# controller15_2.net
KiCad netlist of a schematic drawn in EAGLE
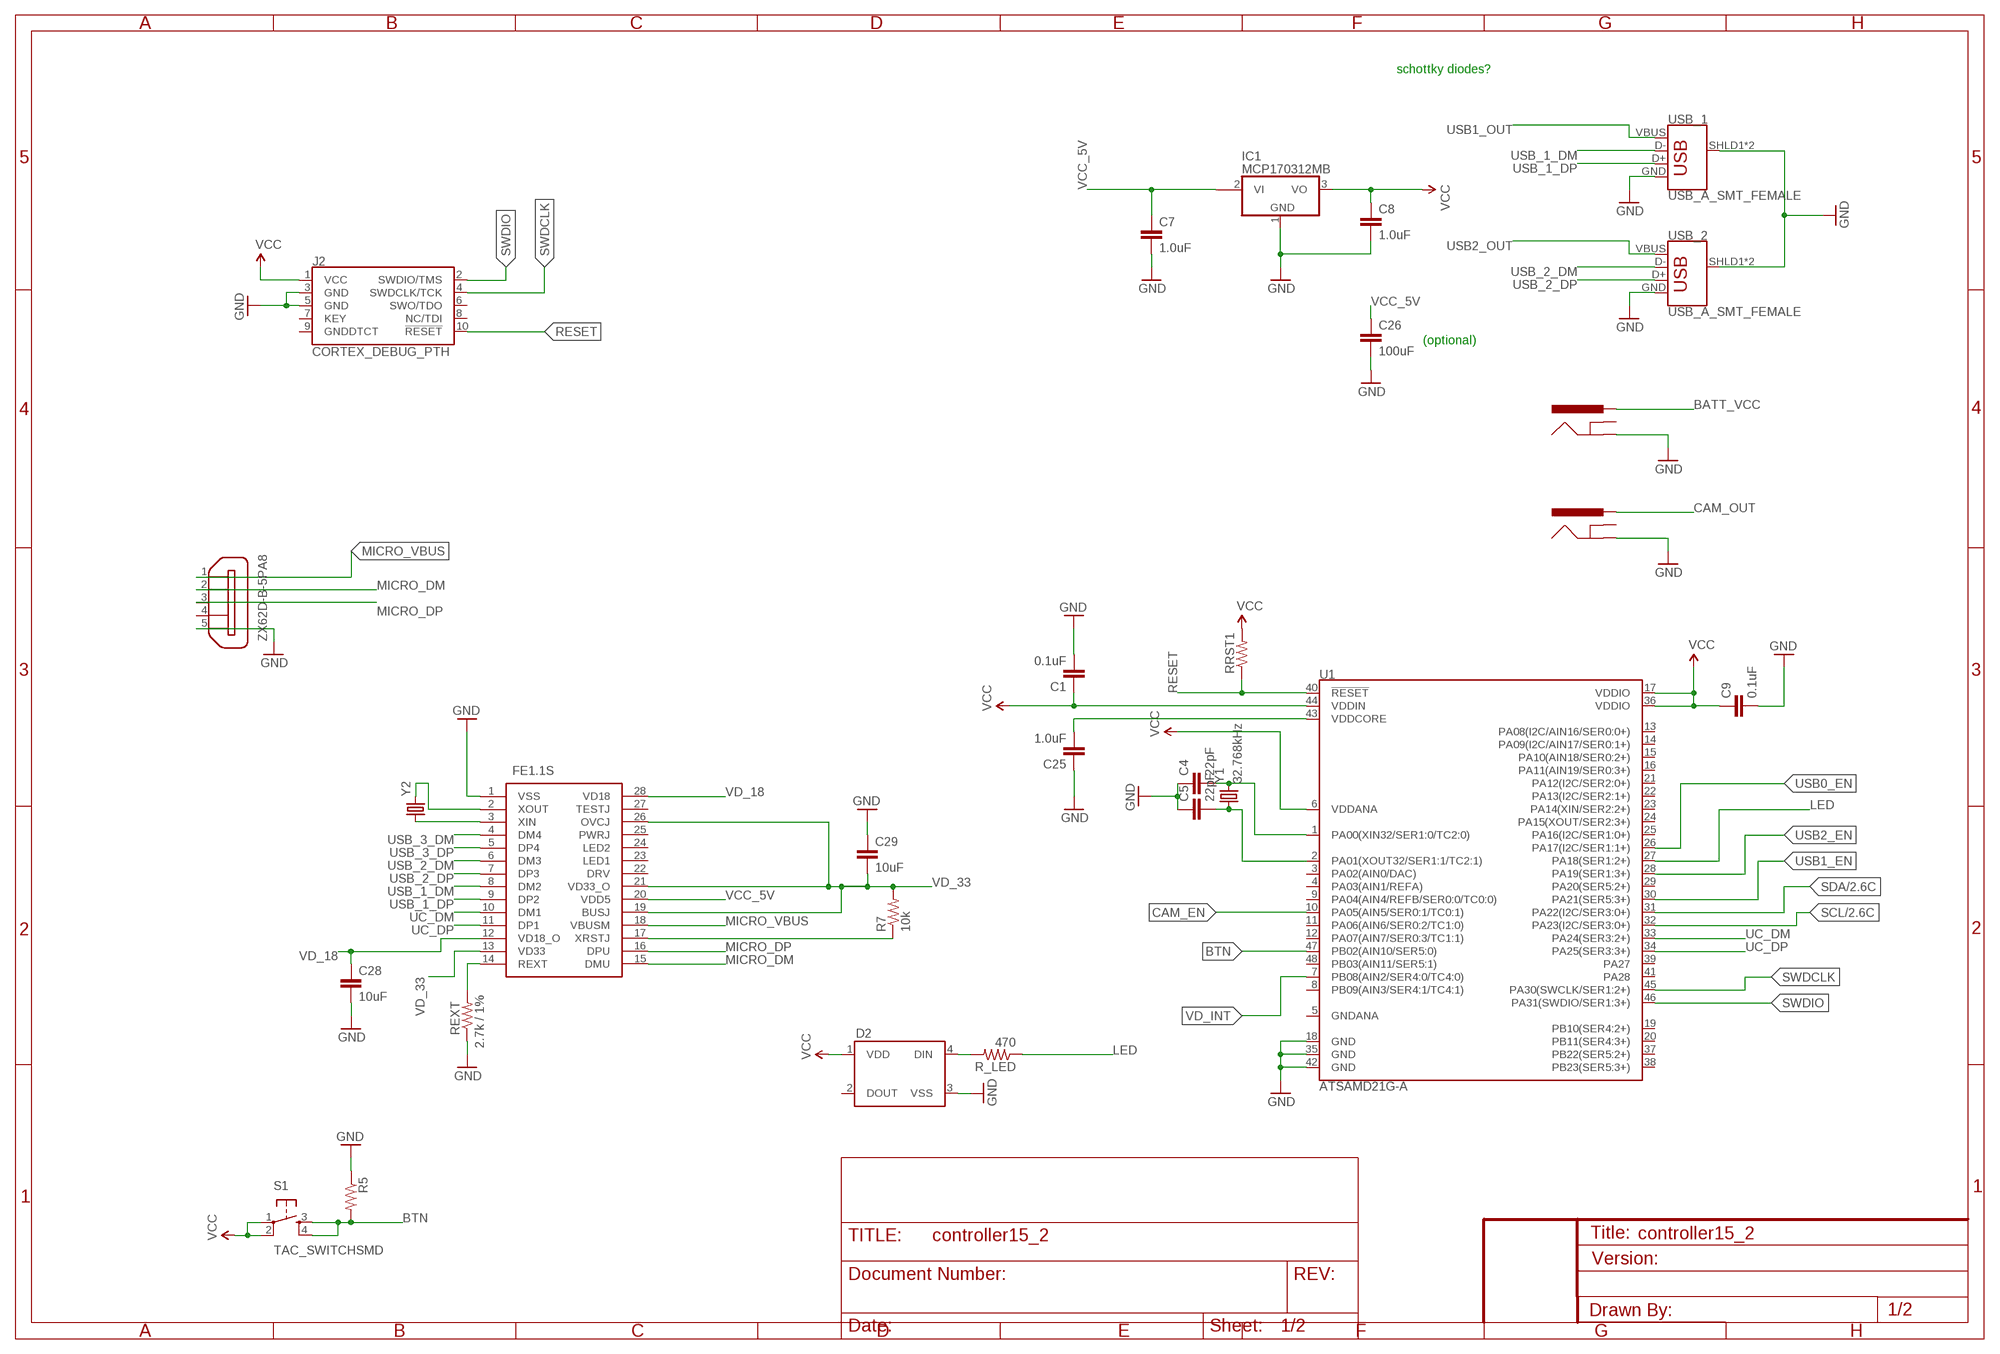
[diagram p0: schematic, sheet 1]
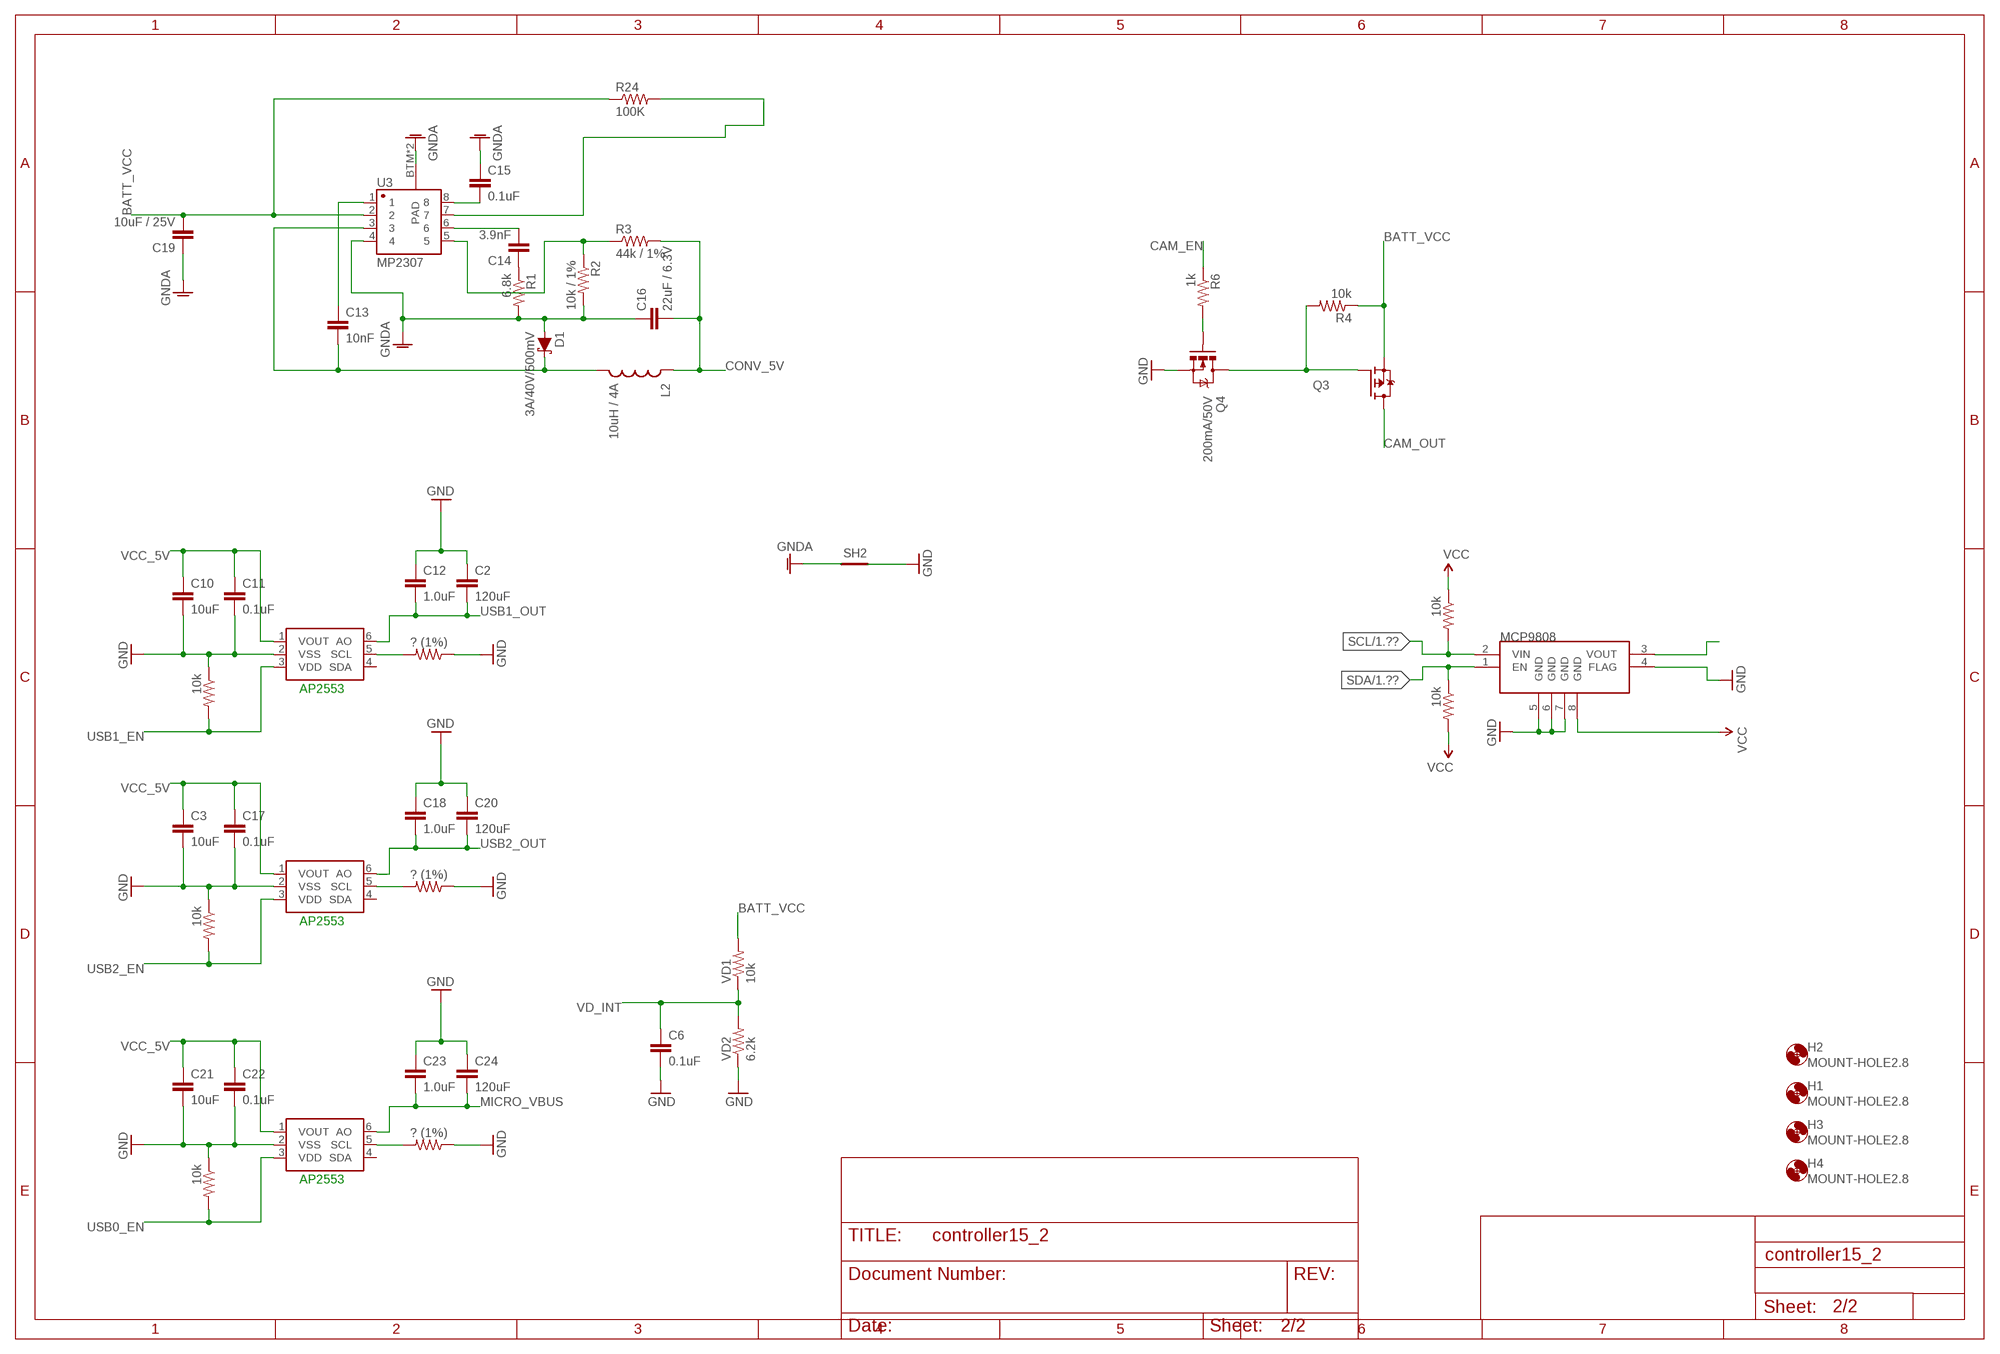
[diagram p1: schematic, sheet 2]

(export (version "E")
  (design (tool "Eeschema 10.0.6"))
  (components
    (comp (ref "C1")
      (value "0.1uF")
      (footprint "eagle-import:0805")
      (libsource (lib "eagle-import") (part "1.0UF-0805-25V-10%"))
    )
    (comp (ref "C4")
      (value "22pF")
      (footprint "eagle-import:0805")
      (libsource (lib "eagle-import") (part "SparkFun-Passives_CAP0805"))
    )
    (comp (ref "C5")
      (value "22pF")
      (footprint "eagle-import:0805")
      (libsource (lib "eagle-import") (part "SparkFun-Passives_CAP0805"))
    )
    (comp (ref "C7")
      (value "1.0uF")
      (footprint "eagle-import:1206")
      (libsource (lib "eagle-import") (part "1.0UF-1206-50V-10%"))
    )
    (comp (ref "C8")
      (value "1.0uF")
      (footprint "eagle-import:1206")
      (libsource (lib "eagle-import") (part "1.0UF-1206-50V-10%"))
    )
    (comp (ref "C9")
      (value "0.1uF")
      (footprint "eagle-import:0805")
      (libsource (lib "eagle-import") (part "1.0UF-0805-25V-10%"))
    )
    (comp (ref "C25")
      (value "1.0uF")
      (footprint "eagle-import:0805")
      (libsource (lib "eagle-import") (part "1.0UF-0805-25V-10%"))
    )
    (comp (ref "C26")
      (value "100uF")
      (footprint "eagle-import:1206")
      (libsource (lib "eagle-import") (part "1.0UF-1206-50V-10%"))
    )
    (comp (ref "C28")
      (value "10uF")
      (footprint "eagle-import:0805")
      (libsource (lib "eagle-import") (part "1.0UF-0805-25V-10%"))
    )
    (comp (ref "C29")
      (value "10uF")
      (footprint "eagle-import:0805")
      (libsource (lib "eagle-import") (part "1.0UF-0805-25V-10%"))
    )
    (comp (ref "D2")
      (value "WS2812B")
      (footprint "eagle-import:WS2812B")
      (libsource (lib "eagle-import") (part "WS2812B"))
    )
    (comp (ref "IC1")
      (value "MCP170312MB")
      (footprint "eagle-import:SOT89")
      (libsource (lib "eagle-import") (part "MCP1703MB12"))
    )
    (comp (ref "IC3")
      (value "FE1.1S")
      (footprint "eagle-import:SOP64P600X175-28N")
      (libsource (lib "eagle-import") (part "FE1.1S"))
    )
    (comp (ref "J2")
      (value "CORTEX_DEBUG_PTH")
      (footprint "eagle-import:2X5-PTH-1.27MM")
      (libsource (lib "eagle-import") (part "CORTEX_DEBUG_PTH"))
    )
    (comp (ref "J3")
      (value "POWER_JACKPTH_BREAD")
      (footprint "eagle-import:POWER_JACK_PTH_BREAD")
      (libsource (lib "eagle-import") (part "POWER_JACKPTH_BREAD"))
    )
    (comp (ref "J4")
      (value "POWER_JACKPTH_BREAD")
      (footprint "eagle-import:POWER_JACK_PTH_BREAD")
      (libsource (lib "eagle-import") (part "POWER_JACKPTH_BREAD"))
    )
    (comp (ref "R5")
      (value "RESISTOR0805-RES")
      (footprint "eagle-import:0805")
      (libsource (lib "eagle-import") (part "RESISTOR0805-RES"))
    )
    (comp (ref "R7")
      (value "10k")
      (footprint "eagle-import:0805")
      (libsource (lib "eagle-import") (part "RESISTOR0805-RES"))
    )
    (comp (ref "REXT")
      (value "2.7k / 1%")
      (footprint "eagle-import:0805")
      (libsource (lib "eagle-import") (part "RESISTOR0805-RES"))
    )
    (comp (ref "RRST1")
      (value "RESISTOR0805-RES")
      (footprint "eagle-import:0805")
      (libsource (lib "eagle-import") (part "RESISTOR0805-RES"))
    )
    (comp (ref "R_LED")
      (value "470")
      (footprint "eagle-import:0805")
      (libsource (lib "eagle-import") (part "SparkFun-Resistors_RESISTOR0805-RES"))
    )
    (comp (ref "S1")
      (value "TAC_SWITCHSMD")
      (footprint "eagle-import:TACTILE-SWITCH-SMD")
      (libsource (lib "eagle-import") (part "TAC_SWITCHSMD"))
    )
    (comp (ref "U1")
      (value "ATSAMD21G-A")
      (footprint "eagle-import:TQFP-48")
      (libsource (lib "eagle-import") (part "ATSAMD21G-A"))
    )
    (comp (ref "USB_1")
      (value "USB_A_SMT_FEMALE")
      (footprint "eagle-import:USB-A-S-SILK-FEMALE")
      (libsource (lib "eagle-import") (part "USB_A_SMT_FEMALE"))
    )
    (comp (ref "USB_2")
      (value "USB_A_SMT_FEMALE")
      (footprint "eagle-import:USB-A-S-SILK-FEMALE")
      (libsource (lib "eagle-import") (part "USB_A_SMT_FEMALE"))
    )
    (comp (ref "X2")
      (value "ZX62D-B-5PA8")
      (footprint "eagle-import:ZX62D-B-5PA8")
      (fields (field (name "MF") "Hirose"))
      (libsource (lib "eagle-import") (part "ZX62D-B-5PA8"))
    )
    (comp (ref "Y1")
      (value "32.768kHz")
      (footprint "eagle-import:CRYSTAL-SMD-3.2X1.5MM")
      (libsource (lib "eagle-import") (part "CRYSTAL3.2X1.5MM"))
    )
    (comp (ref "Y2")
      (value "12MHz")
      (footprint "eagle-import:HC49U-V")
      (libsource (lib "eagle-import") (part "CRYSTALHC49UV"))
    )
    (comp (ref "AP1")
      (value "MCP4725")
      (footprint "eagle-import:SOT23-6")
      (libsource (lib "eagle-import") (part "MCP4725SOT-23"))
    )
    (comp (ref "AP2")
      (value "MCP4725")
      (footprint "eagle-import:SOT23-6")
      (libsource (lib "eagle-import") (part "MCP4725SOT-23"))
    )
    (comp (ref "AP2553")
      (value "MCP4725")
      (footprint "eagle-import:SOT23-6")
      (libsource (lib "eagle-import") (part "MCP4725SOT-23"))
    )
    (comp (ref "C2")
      (value "120uF")
      (footprint "eagle-import:1206")
      (libsource (lib "eagle-import") (part "1.0UF-1206-50V-10%"))
    )
    (comp (ref "C3")
      (value "10uF")
      (footprint "eagle-import:1206")
      (libsource (lib "eagle-import") (part "1.0UF-1206-50V-10%"))
    )
    (comp (ref "C6")
      (value "0.1uF")
      (footprint "eagle-import:1206")
      (libsource (lib "eagle-import") (part "CAP1206"))
    )
    (comp (ref "C10")
      (value "10uF")
      (footprint "eagle-import:1206")
      (libsource (lib "eagle-import") (part "1.0UF-1206-50V-10%"))
    )
    (comp (ref "C11")
      (value "0.1uF")
      (footprint "eagle-import:0805")
      (libsource (lib "eagle-import") (part "1.0UF-0805-25V-10%"))
    )
    (comp (ref "C12")
      (value "1.0uF")
      (footprint "eagle-import:1206")
      (libsource (lib "eagle-import") (part "1.0UF-1206-50V-10%"))
    )
    (comp (ref "C13")
      (value "10nF")
      (footprint "eagle-import:1206")
      (libsource (lib "eagle-import") (part "CAP1206"))
    )
    (comp (ref "C14")
      (value "3.9nF")
      (footprint "eagle-import:1206")
      (libsource (lib "eagle-import") (part "CAP1206"))
    )
    (comp (ref "C15")
      (value "0.1uF")
      (footprint "eagle-import:1206")
      (libsource (lib "eagle-import") (part "CAP1206"))
    )
    (comp (ref "C16")
      (value "22uF / 6.3V")
      (footprint "eagle-import:1210")
      (libsource (lib "eagle-import") (part "CAP1210"))
    )
    (comp (ref "C17")
      (value "0.1uF")
      (footprint "eagle-import:0805")
      (libsource (lib "eagle-import") (part "1.0UF-0805-25V-10%"))
    )
    (comp (ref "C18")
      (value "1.0uF")
      (footprint "eagle-import:1206")
      (libsource (lib "eagle-import") (part "1.0UF-1206-50V-10%"))
    )
    (comp (ref "C19")
      (value "10uF / 25V")
      (footprint "eagle-import:1210")
      (libsource (lib "eagle-import") (part "CAP1210"))
    )
    (comp (ref "C20")
      (value "120uF")
      (footprint "eagle-import:1206")
      (libsource (lib "eagle-import") (part "1.0UF-1206-50V-10%"))
    )
    (comp (ref "C21")
      (value "10uF")
      (footprint "eagle-import:1206")
      (libsource (lib "eagle-import") (part "1.0UF-1206-50V-10%"))
    )
    (comp (ref "C22")
      (value "0.1uF")
      (footprint "eagle-import:0805")
      (libsource (lib "eagle-import") (part "1.0UF-0805-25V-10%"))
    )
    (comp (ref "C23")
      (value "1.0uF")
      (footprint "eagle-import:1206")
      (libsource (lib "eagle-import") (part "1.0UF-1206-50V-10%"))
    )
    (comp (ref "C24")
      (value "120uF")
      (footprint "eagle-import:1206")
      (libsource (lib "eagle-import") (part "1.0UF-1206-50V-10%"))
    )
    (comp (ref "D1")
      (value "3A/40V/500mV")
      (footprint "eagle-import:SMA-DIODE")
      (libsource (lib "eagle-import") (part "DIODE-SCHOTTKY-B340A"))
    )
    (comp (ref "H1")
      (value "MOUNT-HOLE2.8")
      (footprint "eagle-import:2,8")
      (libsource (lib "eagle-import") (part "MOUNT-HOLE2.8"))
    )
    (comp (ref "H2")
      (value "MOUNT-HOLE2.8")
      (footprint "eagle-import:2,8")
      (libsource (lib "eagle-import") (part "MOUNT-HOLE2.8"))
    )
    (comp (ref "H3")
      (value "MOUNT-HOLE2.8")
      (footprint "eagle-import:2,8")
      (libsource (lib "eagle-import") (part "MOUNT-HOLE2.8"))
    )
    (comp (ref "H4")
      (value "MOUNT-HOLE2.8")
      (footprint "eagle-import:2,8")
      (libsource (lib "eagle-import") (part "MOUNT-HOLE2.8"))
    )
    (comp (ref "L2")
      (value "10uH / 4A")
      (footprint "eagle-import:SRU1038")
      (libsource (lib "eagle-import") (part "INDUCTORSRU1038"))
    )
    (comp (ref "MCP9808")
      (value "V_REG_MIC5216")
      (footprint "eagle-import:MSOP8")
      (libsource (lib "eagle-import") (part "V_REG_MIC5216"))
    )
    (comp (ref "Q3")
      (value "FDD4141TO252")
      (footprint "eagle-import:TO252")
      (libsource (lib "eagle-import") (part "FDD4141TO252"))
    )
    (comp (ref "Q4")
      (value "200mA/50V")
      (footprint "eagle-import:SOT23-3")
      (libsource (lib "eagle-import") (part "MOSFET-NCHANNELBSS138"))
    )
    (comp (ref "R1")
      (value "6.8k")
      (footprint "eagle-import:1206")
      (libsource (lib "eagle-import") (part "SparkFun-Resistors_RESISTOR1206"))
    )
    (comp (ref "R2")
      (value "10k / 1%")
      (footprint "eagle-import:1206")
      (libsource (lib "eagle-import") (part "SparkFun-Resistors_RESISTOR1206"))
    )
    (comp (ref "R3")
      (value "44k / 1%")
      (footprint "eagle-import:1206")
      (libsource (lib "eagle-import") (part "SparkFun-Resistors_RESISTOR1206"))
    )
    (comp (ref "R4")
      (value "10k")
      (footprint "eagle-import:0805")
      (libsource (lib "eagle-import") (part "SparkFun-Resistors_RESISTOR0805-RES"))
    )
    (comp (ref "R6")
      (value "1k")
      (footprint "eagle-import:0805")
      (libsource (lib "eagle-import") (part "SparkFun-Resistors_RESISTOR0805-RES"))
    )
    (comp (ref "R24")
      (value "100K")
      (footprint "eagle-import:1206")
      (libsource (lib "eagle-import") (part "SparkFun-Resistors_RESISTOR1206"))
    )
    (comp (ref "R_I2C_1")
      (value "10k")
      (footprint "eagle-import:0805")
      (libsource (lib "eagle-import") (part "RESISTOR0805-RES"))
    )
    (comp (ref "R_I2C_2")
      (value "10k")
      (footprint "eagle-import:0805")
      (libsource (lib "eagle-import") (part "RESISTOR0805-RES"))
    )
    (comp (ref "R_MOSFET_USB1")
      (value "? (1%)")
      (footprint "eagle-import:0805")
      (libsource (lib "eagle-import") (part "RESISTOR0805-RES"))
    )
    (comp (ref "R_MOSFET_USB2")
      (value "? (1%)")
      (footprint "eagle-import:0805")
      (libsource (lib "eagle-import") (part "RESISTOR0805-RES"))
    )
    (comp (ref "R_MOSFET_USB3")
      (value "10k")
      (footprint "eagle-import:0805")
      (libsource (lib "eagle-import") (part "RESISTOR0805-RES"))
    )
    (comp (ref "R_MOSFET_USB4")
      (value "10k")
      (footprint "eagle-import:0805")
      (libsource (lib "eagle-import") (part "RESISTOR0805-RES"))
    )
    (comp (ref "R_MOSFET_USB5")
      (value "? (1%)")
      (footprint "eagle-import:0805")
      (libsource (lib "eagle-import") (part "RESISTOR0805-RES"))
    )
    (comp (ref "R_MOSFET_USB6")
      (value "10k")
      (footprint "eagle-import:0805")
      (libsource (lib "eagle-import") (part "RESISTOR0805-RES"))
    )
    (comp (ref "SH2")
      (value "SHORT-HT5")
      (footprint "eagle-import:SHORT_TOP-50")
      (libsource (lib "eagle-import") (part "SHORT-HT5"))
    )
    (comp (ref "U3")
      (value "MP2307")
      (footprint "eagle-import:SO08")
      (libsource (lib "eagle-import") (part "GENERIC-SOIC8MSGEQ7N-FILTER"))
    )
    (comp (ref "VD1")
      (value "10k")
      (footprint "eagle-import:1206")
      (libsource (lib "eagle-import") (part "RESISTOR1206"))
    )
    (comp (ref "VD2")
      (value "6.2k")
      (footprint "eagle-import:1206")
      (libsource (lib "eagle-import") (part "RESISTOR1206"))
    )
  )
  (nets
    (net (code "1") (name "BATT_VCC") (class "Default")
      (node (ref "C19") (pin "2") (pinfunction "2_2") (pintype "passive"))
      (node (ref "J4") (pin "PWR") (pinfunction "PWR_PWR") (pintype "bidirectional"))
      (node (ref "Q3") (pin "2") (pinfunction "S_2") (pintype "passive"))
      (node (ref "R24") (pin "1") (pinfunction "1_1") (pintype "passive"))
      (node (ref "R4") (pin "1") (pinfunction "1_1") (pintype "passive"))
      (node (ref "U3") (pin "2") (pinfunction "2_2") (pintype "bidirectional"))
      (node (ref "VD1") (pin "2") (pinfunction "2_2") (pintype "passive"))
    )
    (net (code "2") (name "BTN") (class "Default")
      (node (ref "R5") (pin "2") (pinfunction "2_2") (pintype "passive"))
      (node (ref "S1") (pin "3") (pinfunction "3_3") (pintype "passive"))
      (node (ref "S1") (pin "4") (pinfunction "4_4") (pintype "passive"))
      (node (ref "U1") (pin "47") (pinfunction "PB02(AIN10/SER5:0)_47") (pintype "bidirectional"))
    )
    (net (code "3") (name "CAM_EN") (class "Default")
      (node (ref "R6") (pin "1") (pinfunction "1_1") (pintype "passive"))
      (node (ref "U1") (pin "10") (pinfunction "PA05(AIN5/SER0:1/TC0:1)_10") (pintype "bidirectional"))
    )
    (net (code "4") (name "CAM_OUT") (class "Default")
      (node (ref "J3") (pin "PWR") (pinfunction "PWR_PWR") (pintype "bidirectional"))
      (node (ref "Q3") (pin "3") (pinfunction "D_3") (pintype "passive"))
    )
    (net (code "5") (name "CONV_5V") (class "Default")
      (node (ref "C16") (pin "2") (pinfunction "2_2") (pintype "passive"))
      (node (ref "L2") (pin "1") (pinfunction "1_1") (pintype "passive"))
      (node (ref "R3") (pin "2") (pinfunction "2_2") (pintype "passive"))
    )
    (net (code "6") (name "GND") (class "Default")
      (node (ref "AP1") (pin "2") (pinfunction "VSS_2") (pintype "bidirectional"))
      (node (ref "AP2") (pin "2") (pinfunction "VSS_2") (pintype "bidirectional"))
      (node (ref "AP2553") (pin "2") (pinfunction "VSS_2") (pintype "bidirectional"))
      (node (ref "C1") (pin "2") (pinfunction "2_2") (pintype "passive"))
      (node (ref "C10") (pin "2") (pinfunction "2_2") (pintype "passive"))
      (node (ref "C11") (pin "2") (pinfunction "2_2") (pintype "passive"))
      (node (ref "C12") (pin "1") (pinfunction "1_1") (pintype "passive"))
      (node (ref "C17") (pin "2") (pinfunction "2_2") (pintype "passive"))
      (node (ref "C18") (pin "1") (pinfunction "1_1") (pintype "passive"))
      (node (ref "C2") (pin "1") (pinfunction "1_1") (pintype "passive"))
      (node (ref "C20") (pin "1") (pinfunction "1_1") (pintype "passive"))
      (node (ref "C21") (pin "2") (pinfunction "2_2") (pintype "passive"))
      (node (ref "C22") (pin "2") (pinfunction "2_2") (pintype "passive"))
      (node (ref "C23") (pin "1") (pinfunction "1_1") (pintype "passive"))
      (node (ref "C24") (pin "1") (pinfunction "1_1") (pintype "passive"))
      (node (ref "C25") (pin "1") (pinfunction "1_1") (pintype "passive"))
      (node (ref "C26") (pin "2") (pinfunction "2_2") (pintype "passive"))
      (node (ref "C28") (pin "2") (pinfunction "2_2") (pintype "passive"))
      (node (ref "C29") (pin "1") (pinfunction "1_1") (pintype "passive"))
      (node (ref "C3") (pin "2") (pinfunction "2_2") (pintype "passive"))
      (node (ref "C4") (pin "1") (pinfunction "1_1") (pintype "passive"))
      (node (ref "C5") (pin "1") (pinfunction "1_1") (pintype "passive"))
      (node (ref "C6") (pin "2") (pinfunction "2_2") (pintype "passive"))
      (node (ref "C7") (pin "2") (pinfunction "2_2") (pintype "passive"))
      (node (ref "C8") (pin "2") (pinfunction "2_2") (pintype "passive"))
      (node (ref "C9") (pin "2") (pinfunction "2_2") (pintype "passive"))
      (node (ref "D2") (pin "3") (pinfunction "VSS_3") (pintype "power_in"))
      (node (ref "IC1") (pin "1") (pinfunction "GND_1") (pintype "passive"))
      (node (ref "IC3") (pin "1") (pinfunction "VSS_1") (pintype "bidirectional"))
      (node (ref "J2") (pin "3") (pinfunction "GND_3") (pintype "bidirectional"))
      (node (ref "J2") (pin "5") (pinfunction "GND_5") (pintype "bidirectional"))
      (node (ref "J3") (pin "GND") (pinfunction "GND_GND") (pintype "bidirectional"))
      (node (ref "J4") (pin "GND") (pinfunction "GND_GND") (pintype "bidirectional"))
      (node (ref "MCP9808") (pin "4") (pinfunction "FLAG_4") (pintype "bidirectional"))
      (node (ref "MCP9808") (pin "5") (pinfunction "GND_5") (pintype "bidirectional"))
      (node (ref "MCP9808") (pin "6") (pinfunction "GND_6") (pintype "bidirectional"))
      (node (ref "MCP9808") (pin "7") (pinfunction "GND_7") (pintype "bidirectional"))
      (node (ref "Q4") (pin "2") (pinfunction "S_2") (pintype "passive"))
      (node (ref "R5") (pin "1") (pinfunction "1_1") (pintype "passive"))
      (node (ref "REXT") (pin "1") (pinfunction "1_1") (pintype "passive"))
      (node (ref "R_MOSFET_USB1") (pin "1") (pinfunction "1_1") (pintype "passive"))
      (node (ref "R_MOSFET_USB2") (pin "1") (pinfunction "1_1") (pintype "passive"))
      (node (ref "R_MOSFET_USB3") (pin "1") (pinfunction "1_1") (pintype "passive"))
      (node (ref "R_MOSFET_USB4") (pin "1") (pinfunction "1_1") (pintype "passive"))
      (node (ref "R_MOSFET_USB5") (pin "1") (pinfunction "1_1") (pintype "passive"))
      (node (ref "R_MOSFET_USB6") (pin "1") (pinfunction "1_1") (pintype "passive"))
      (node (ref "SH2") (pin "2") (pinfunction "P$2_2") (pintype "bidirectional"))
      (node (ref "U1") (pin "18") (pinfunction "GND_18") (pintype "bidirectional"))
      (node (ref "U1") (pin "35") (pinfunction "GND_35") (pintype "bidirectional"))
      (node (ref "U1") (pin "42") (pinfunction "GND_42") (pintype "bidirectional"))
      (node (ref "USB_1") (pin "GND") (pinfunction "GND_GND") (pintype "power_in"))
      (node (ref "USB_1") (pin "SHLD1") (pinfunction "SHIELD_SHLD1") (pintype "bidirectional"))
      (node (ref "USB_1") (pin "SHLD2") (pinfunction "SHIELD_SHLD2") (pintype "bidirectional"))
      (node (ref "USB_2") (pin "GND") (pinfunction "GND_GND") (pintype "power_in"))
      (node (ref "USB_2") (pin "SHLD1") (pinfunction "SHIELD_SHLD1") (pintype "bidirectional"))
      (node (ref "USB_2") (pin "SHLD2") (pinfunction "SHIELD_SHLD2") (pintype "bidirectional"))
      (node (ref "VD2") (pin "1") (pinfunction "1_1") (pintype "passive"))
      (node (ref "X2") (pin "5") (pinfunction "5_5") (pintype "passive"))
    )
    (net (code "7") (name "GNDA") (class "Default")
      (node (ref "C15") (pin "1") (pinfunction "1_1") (pintype "passive"))
      (node (ref "C16") (pin "1") (pinfunction "1_1") (pintype "passive"))
      (node (ref "C19") (pin "1") (pinfunction "1_1") (pintype "passive"))
      (node (ref "D1") (pin "A") (pinfunction "A_A") (pintype "passive"))
      (node (ref "R1") (pin "2") (pinfunction "2_2") (pintype "passive"))
      (node (ref "R2") (pin "2") (pinfunction "2_2") (pintype "passive"))
      (node (ref "SH2") (pin "1") (pinfunction "P$1_1") (pintype "bidirectional"))
      (node (ref "U3") (pin "4") (pinfunction "4_4") (pintype "bidirectional"))
      (node (ref "U3") (pin "BTM") (pinfunction "PAD_BTM") (pintype "bidirectional"))
      (node (ref "U3") (pin "P$1") (pinfunction "PAD_P$1") (pintype "bidirectional"))
    )
    (net (code "8") (name "LED") (class "Default")
      (node (ref "R_LED") (pin "1") (pinfunction "1_1") (pintype "passive"))
      (node (ref "U1") (pin "27") (pinfunction "PA18(SER1:2+)_27") (pintype "bidirectional"))
    )
    (net (code "9") (name "MICRO_DM") (class "Default")
      (node (ref "IC3") (pin "15") (pinfunction "DMU_15") (pintype "bidirectional"))
      (node (ref "X2") (pin "2") (pinfunction "2_2") (pintype "passive"))
    )
    (net (code "10") (name "MICRO_DP") (class "Default")
      (node (ref "IC3") (pin "16") (pinfunction "DPU_16") (pintype "bidirectional"))
      (node (ref "X2") (pin "3") (pinfunction "3_3") (pintype "passive"))
    )
    (net (code "11") (name "MICRO_VBUS") (class "Default")
      (node (ref "AP2") (pin "6") (pinfunction "AO_6") (pintype "bidirectional"))
      (node (ref "C23") (pin "2") (pinfunction "2_2") (pintype "passive"))
      (node (ref "C24") (pin "2") (pinfunction "2_2") (pintype "passive"))
      (node (ref "IC3") (pin "18") (pinfunction "VBUSM_18") (pintype "bidirectional"))
      (node (ref "X2") (pin "1") (pinfunction "1_1") (pintype "passive"))
    )
    (net (code "12") (name "Net-(AP1-SCL)") (class "Default")
      (node (ref "AP1") (pin "5") (pinfunction "SCL_5") (pintype "bidirectional"))
      (node (ref "R_MOSFET_USB2") (pin "2") (pinfunction "2_2") (pintype "passive"))
    )
    (net (code "13") (name "Net-(AP2-SCL)") (class "Default")
      (node (ref "AP2") (pin "5") (pinfunction "SCL_5") (pintype "bidirectional"))
      (node (ref "R_MOSFET_USB5") (pin "2") (pinfunction "2_2") (pintype "passive"))
    )
    (net (code "14") (name "Net-(AP2553-SCL)") (class "Default")
      (node (ref "AP2553") (pin "5") (pinfunction "SCL_5") (pintype "bidirectional"))
      (node (ref "R_MOSFET_USB1") (pin "2") (pinfunction "2_2") (pintype "passive"))
    )
    (net (code "15") (name "Net-(C13-Pad1)") (class "Default")
      (node (ref "C13") (pin "1") (pinfunction "1_1") (pintype "passive"))
      (node (ref "U3") (pin "1") (pinfunction "1_1") (pintype "bidirectional"))
    )
    (net (code "16") (name "Net-(C13-Pad2)") (class "Default")
      (node (ref "C13") (pin "2") (pinfunction "2_2") (pintype "passive"))
      (node (ref "D1") (pin "C") (pinfunction "C_C") (pintype "passive"))
      (node (ref "L2") (pin "2") (pinfunction "2_2") (pintype "passive"))
      (node (ref "U3") (pin "3") (pinfunction "3_3") (pintype "bidirectional"))
    )
    (net (code "17") (name "Net-(C14-Pad1)") (class "Default")
      (node (ref "C14") (pin "1") (pinfunction "1_1") (pintype "passive"))
      (node (ref "R1") (pin "1") (pinfunction "1_1") (pintype "passive"))
    )
    (net (code "18") (name "Net-(C14-Pad2)") (class "Default")
      (node (ref "C14") (pin "2") (pinfunction "2_2") (pintype "passive"))
      (node (ref "U3") (pin "6") (pinfunction "6_6") (pintype "bidirectional"))
    )
    (net (code "19") (name "Net-(C15-Pad2)") (class "Default")
      (node (ref "C15") (pin "2") (pinfunction "2_2") (pintype "passive"))
      (node (ref "U3") (pin "8") (pinfunction "8_8") (pintype "bidirectional"))
    )
    (net (code "20") (name "Net-(D2-DIN)") (class "Default")
      (node (ref "D2") (pin "4") (pinfunction "DIN_4") (pintype "input"))
      (node (ref "R_LED") (pin "2") (pinfunction "2_2") (pintype "passive"))
    )
    (net (code "21") (name "Net-(IC3-REXT)") (class "Default")
      (node (ref "IC3") (pin "14") (pinfunction "REXT_14") (pintype "bidirectional"))
      (node (ref "REXT") (pin "2") (pinfunction "2_2") (pintype "passive"))
    )
    (net (code "22") (name "Net-(IC3-XIN)") (class "Default")
      (node (ref "IC3") (pin "3") (pinfunction "XIN_3") (pintype "bidirectional"))
      (node (ref "Y2") (pin "1") (pinfunction "1_1") (pintype "passive"))
    )
    (net (code "23") (name "Net-(IC3-XOUT)") (class "Default")
      (node (ref "IC3") (pin "2") (pinfunction "XOUT_2") (pintype "bidirectional"))
      (node (ref "Y2") (pin "2") (pinfunction "2_2") (pintype "passive"))
    )
    (net (code "24") (name "Net-(IC3-XRSTJ)") (class "Default")
      (node (ref "IC3") (pin "17") (pinfunction "XRSTJ_17") (pintype "bidirectional"))
      (node (ref "R7") (pin "1") (pinfunction "1_1") (pintype "passive"))
    )
    (net (code "25") (name "Net-(Q3-G)") (class "Default")
      (node (ref "Q3") (pin "1") (pinfunction "G_1") (pintype "passive"))
      (node (ref "Q4") (pin "3") (pinfunction "D_3") (pintype "passive"))
      (node (ref "R4") (pin "2") (pinfunction "2_2") (pintype "passive"))
    )
    (net (code "26") (name "Net-(Q4-G)") (class "Default")
      (node (ref "Q4") (pin "1") (pinfunction "G_1") (pintype "passive"))
      (node (ref "R6") (pin "2") (pinfunction "2_2") (pintype "passive"))
    )
    (net (code "27") (name "Net-(R2-Pad1)") (class "Default")
      (node (ref "R2") (pin "1") (pinfunction "1_1") (pintype "passive"))
      (node (ref "R3") (pin "1") (pinfunction "1_1") (pintype "passive"))
      (node (ref "U3") (pin "5") (pinfunction "5_5") (pintype "bidirectional"))
    )
    (net (code "28") (name "Net-(R24-Pad2)") (class "Default")
      (node (ref "R24") (pin "2") (pinfunction "2_2") (pintype "passive"))
      (node (ref "U3") (pin "7") (pinfunction "7_7") (pintype "bidirectional"))
    )
    (net (code "29") (name "Net-(U1-PA00(XIN32{slash}SER1:0{slash}TC2:0))") (class "Default")
      (node (ref "C4") (pin "2") (pinfunction "2_2") (pintype "passive"))
      (node (ref "U1") (pin "1") (pinfunction "PA00(XIN32/SER1:0/TC2:0)_1") (pintype "bidirectional"))
      (node (ref "Y1") (pin "P$2") (pinfunction "2_P$2") (pintype "passive"))
    )
    (net (code "30") (name "Net-(U1-PA01(XOUT32{slash}SER1:1{slash}TC2:1))") (class "Default")
      (node (ref "C5") (pin "2") (pinfunction "2_2") (pintype "passive"))
      (node (ref "U1") (pin "2") (pinfunction "PA01(XOUT32/SER1:1/TC2:1)_2") (pintype "bidirectional"))
      (node (ref "Y1") (pin "P$1") (pinfunction "1_P$1") (pintype "passive"))
    )
    (net (code "31") (name "Net-(U1-VDDCORE)") (class "Default")
      (node (ref "C25") (pin "2") (pinfunction "2_2") (pintype "passive"))
      (node (ref "U1") (pin "43") (pinfunction "VDDCORE_43") (pintype "bidirectional"))
    )
    (net (code "32") (name "RESET") (class "Default")
      (node (ref "J2") (pin "10") (pinfunction "~{RESET}_10") (pintype "bidirectional"))
      (node (ref "RRST1") (pin "1") (pinfunction "1_1") (pintype "passive"))
      (node (ref "U1") (pin "40") (pinfunction "~{RESET}_40") (pintype "bidirectional"))
    )
    (net (code "33") (name "SCL") (class "Default")
      (node (ref "MCP9808") (pin "2") (pinfunction "VIN_2") (pintype "bidirectional"))
      (node (ref "R_I2C_1") (pin "2") (pinfunction "2_2") (pintype "passive"))
      (node (ref "U1") (pin "32") (pinfunction "PA23(I2C/SER3:0+)_32") (pintype "bidirectional"))
    )
    (net (code "34") (name "SDA") (class "Default")
      (node (ref "MCP9808") (pin "1") (pinfunction "EN_1") (pintype "bidirectional"))
      (node (ref "R_I2C_2") (pin "1") (pinfunction "1_1") (pintype "passive"))
      (node (ref "U1") (pin "31") (pinfunction "PA22(I2C/SER3:0+)_31") (pintype "bidirectional"))
    )
    (net (code "35") (name "SWDCLK") (class "Default")
      (node (ref "J2") (pin "4") (pinfunction "SWDCLK/TCK_4") (pintype "bidirectional"))
      (node (ref "U1") (pin "45") (pinfunction "PA30(SWCLK/SER1:2+)_45") (pintype "bidirectional"))
    )
    (net (code "36") (name "SWDIO") (class "Default")
      (node (ref "J2") (pin "2") (pinfunction "SWDIO/TMS_2") (pintype "bidirectional"))
      (node (ref "U1") (pin "46") (pinfunction "PA31(SWDIO/SER1:3+)_46") (pintype "bidirectional"))
    )
    (net (code "37") (name "UC_DM") (class "Default")
      (node (ref "IC3") (pin "10") (pinfunction "DM1_10") (pintype "bidirectional"))
      (node (ref "U1") (pin "33") (pinfunction "PA24(SER3:2+)_33") (pintype "bidirectional"))
    )
    (net (code "38") (name "UC_DP") (class "Default")
      (node (ref "IC3") (pin "11") (pinfunction "DP1_11") (pintype "bidirectional"))
      (node (ref "U1") (pin "34") (pinfunction "PA25(SER3:3+)_34") (pintype "bidirectional"))
    )
    (net (code "39") (name "USB0_EN") (class "Default")
      (node (ref "AP2") (pin "3") (pinfunction "VDD_3") (pintype "bidirectional"))
      (node (ref "R_MOSFET_USB6") (pin "2") (pinfunction "2_2") (pintype "passive"))
      (node (ref "U1") (pin "26") (pinfunction "PA17(I2C/SER1:1+)_26") (pintype "bidirectional"))
    )
    (net (code "40") (name "USB1_EN") (class "Default")
      (node (ref "AP2553") (pin "3") (pinfunction "VDD_3") (pintype "bidirectional"))
      (node (ref "R_MOSFET_USB3") (pin "2") (pinfunction "2_2") (pintype "passive"))
      (node (ref "U1") (pin "30") (pinfunction "PA21(SER5:3+)_30") (pintype "bidirectional"))
    )
    (net (code "41") (name "USB1_OUT") (class "Default")
      (node (ref "AP2553") (pin "6") (pinfunction "AO_6") (pintype "bidirectional"))
      (node (ref "C12") (pin "2") (pinfunction "2_2") (pintype "passive"))
      (node (ref "C2") (pin "2") (pinfunction "2_2") (pintype "passive"))
      (node (ref "USB_1") (pin "VBUS") (pinfunction "VBUS_VBUS") (pintype "power_in"))
    )
    (net (code "42") (name "USB2_EN") (class "Default")
      (node (ref "AP1") (pin "3") (pinfunction "VDD_3") (pintype "bidirectional"))
      (node (ref "R_MOSFET_USB4") (pin "2") (pinfunction "2_2") (pintype "passive"))
      (node (ref "U1") (pin "28") (pinfunction "PA19(SER1:3+)_28") (pintype "bidirectional"))
    )
    (net (code "43") (name "USB2_OUT") (class "Default")
      (node (ref "AP1") (pin "6") (pinfunction "AO_6") (pintype "bidirectional"))
      (node (ref "C18") (pin "2") (pinfunction "2_2") (pintype "passive"))
      (node (ref "C20") (pin "2") (pinfunction "2_2") (pintype "passive"))
      (node (ref "USB_2") (pin "VBUS") (pinfunction "VBUS_VBUS") (pintype "power_in"))
    )
    (net (code "44") (name "USB_1_DM") (class "Default")
      (node (ref "IC3") (pin "8") (pinfunction "DM2_8") (pintype "bidirectional"))
      (node (ref "USB_1") (pin "D-") (pinfunction "D-_D-") (pintype "bidirectional"))
    )
    (net (code "45") (name "USB_1_DP") (class "Default")
      (node (ref "IC3") (pin "9") (pinfunction "DP2_9") (pintype "bidirectional"))
      (node (ref "USB_1") (pin "D+") (pinfunction "D+_D+") (pintype "bidirectional"))
    )
    (net (code "46") (name "USB_2_DM") (class "Default")
      (node (ref "IC3") (pin "6") (pinfunction "DM3_6") (pintype "bidirectional"))
      (node (ref "USB_2") (pin "D-") (pinfunction "D-_D-") (pintype "bidirectional"))
    )
    (net (code "47") (name "USB_2_DP") (class "Default")
      (node (ref "IC3") (pin "7") (pinfunction "DP3_7") (pintype "bidirectional"))
      (node (ref "USB_2") (pin "D+") (pinfunction "D+_D+") (pintype "bidirectional"))
    )
    (net (code "48") (name "USB_3_DM") (class "Default")
      (node (ref "IC3") (pin "4") (pinfunction "DM4_4") (pintype "bidirectional"))
    )
    (net (code "49") (name "USB_3_DP") (class "Default")
      (node (ref "IC3") (pin "5") (pinfunction "DP4_5") (pintype "bidirectional"))
    )
    (net (code "50") (name "VCC") (class "Default")
      (node (ref "C1") (pin "1") (pinfunction "1_1") (pintype "passive"))
      (node (ref "C8") (pin "1") (pinfunction "1_1") (pintype "passive"))
      (node (ref "C9") (pin "1") (pinfunction "1_1") (pintype "passive"))
      (node (ref "D2") (pin "1") (pinfunction "VDD_1") (pintype "power_in"))
      (node (ref "IC1") (pin "3") (pinfunction "VO_3") (pintype "passive"))
      (node (ref "J2") (pin "1") (pinfunction "VCC_1") (pintype "bidirectional"))
      (node (ref "MCP9808") (pin "8") (pinfunction "GND_8") (pintype "bidirectional"))
      (node (ref "RRST1") (pin "2") (pinfunction "2_2") (pintype "passive"))
      (node (ref "R_I2C_1") (pin "1") (pinfunction "1_1") (pintype "passive"))
      (node (ref "R_I2C_2") (pin "2") (pinfunction "2_2") (pintype "passive"))
      (node (ref "S1") (pin "1") (pinfunction "1_1") (pintype "passive"))
      (node (ref "S1") (pin "2") (pinfunction "2_2") (pintype "passive"))
      (node (ref "U1") (pin "17") (pinfunction "VDDIO_17") (pintype "bidirectional"))
      (node (ref "U1") (pin "36") (pinfunction "VDDIO_36") (pintype "bidirectional"))
      (node (ref "U1") (pin "44") (pinfunction "VDDIN_44") (pintype "bidirectional"))
      (node (ref "U1") (pin "6") (pinfunction "VDDANA_6") (pintype "bidirectional"))
    )
    (net (code "51") (name "VCC_5V") (class "Default")
      (node (ref "AP1") (pin "1") (pinfunction "VOUT_1") (pintype "bidirectional"))
      (node (ref "AP2") (pin "1") (pinfunction "VOUT_1") (pintype "bidirectional"))
      (node (ref "AP2553") (pin "1") (pinfunction "VOUT_1") (pintype "bidirectional"))
      (node (ref "C10") (pin "1") (pinfunction "1_1") (pintype "passive"))
      (node (ref "C11") (pin "1") (pinfunction "1_1") (pintype "passive"))
      (node (ref "C17") (pin "1") (pinfunction "1_1") (pintype "passive"))
      (node (ref "C21") (pin "1") (pinfunction "1_1") (pintype "passive"))
      (node (ref "C22") (pin "1") (pinfunction "1_1") (pintype "passive"))
      (node (ref "C26") (pin "1") (pinfunction "1_1") (pintype "passive"))
      (node (ref "C3") (pin "1") (pinfunction "1_1") (pintype "passive"))
      (node (ref "C7") (pin "1") (pinfunction "1_1") (pintype "passive"))
      (node (ref "IC1") (pin "2@1") (pinfunction "VI1_2@1") (pintype "input"))
      (node (ref "IC3") (pin "20") (pinfunction "VDD5_20") (pintype "bidirectional"))
    )
    (net (code "52") (name "VD_18") (class "Default")
      (node (ref "C28") (pin "1") (pinfunction "1_1") (pintype "passive"))
      (node (ref "IC3") (pin "12") (pinfunction "VD18_O_12") (pintype "bidirectional"))
      (node (ref "IC3") (pin "28") (pinfunction "VD18_28") (pintype "bidirectional"))
    )
    (net (code "53") (name "VD_33") (class "Default")
      (node (ref "C29") (pin "2") (pinfunction "2_2") (pintype "passive"))
      (node (ref "IC3") (pin "13") (pinfunction "VD33_13") (pintype "bidirectional"))
      (node (ref "IC3") (pin "19") (pinfunction "BUSJ_19") (pintype "bidirectional"))
      (node (ref "IC3") (pin "21") (pinfunction "VD33_O_21") (pintype "bidirectional"))
      (node (ref "IC3") (pin "26") (pinfunction "OVCJ_26") (pintype "bidirectional"))
      (node (ref "R7") (pin "2") (pinfunction "2_2") (pintype "passive"))
    )
    (net (code "54") (name "VD_INT") (class "Default")
      (node (ref "C6") (pin "1") (pinfunction "1_1") (pintype "passive"))
      (node (ref "U1") (pin "7") (pinfunction "PB08(AIN2/SER4:0/TC4:0)_7") (pintype "bidirectional"))
      (node (ref "VD1") (pin "1") (pinfunction "1_1") (pintype "passive"))
      (node (ref "VD2") (pin "2") (pinfunction "2_2") (pintype "passive"))
    )
    (net (code "55") (name "unconnected-(AP1-SDA-Pad4)") (class "Default")
      (node (ref "AP1") (pin "4") (pinfunction "SDA_4") (pintype "bidirectional"))
    )
    (net (code "56") (name "unconnected-(AP2-SDA-Pad4)") (class "Default")
      (node (ref "AP2") (pin "4") (pinfunction "SDA_4") (pintype "bidirectional"))
    )
    (net (code "57") (name "unconnected-(AP2553-SDA-Pad4)") (class "Default")
      (node (ref "AP2553") (pin "4") (pinfunction "SDA_4") (pintype "bidirectional"))
    )
    (net (code "58") (name "unconnected-(D2-DOUT-Pad2)") (class "Default")
      (node (ref "D2") (pin "2") (pinfunction "DOUT_2") (pintype "output"))
    )
    (net (code "59") (name "unconnected-(IC1-VI-Pad2)") (class "Default")
      (node (ref "IC1") (pin "2") (pinfunction "VI_2") (pintype "input"))
    )
    (net (code "60") (name "unconnected-(IC3-DRV-Pad22)") (class "Default")
      (node (ref "IC3") (pin "22") (pinfunction "DRV_22") (pintype "bidirectional"))
    )
    (net (code "61") (name "unconnected-(IC3-LED1-Pad23)") (class "Default")
      (node (ref "IC3") (pin "23") (pinfunction "LED1_23") (pintype "bidirectional"))
    )
    (net (code "62") (name "unconnected-(IC3-LED2-Pad24)") (class "Default")
      (node (ref "IC3") (pin "24") (pinfunction "LED2_24") (pintype "bidirectional"))
    )
    (net (code "63") (name "unconnected-(IC3-PWRJ-Pad25)") (class "Default")
      (node (ref "IC3") (pin "25") (pinfunction "PWRJ_25") (pintype "bidirectional"))
    )
    (net (code "64") (name "unconnected-(IC3-TESTJ-Pad27)") (class "Default")
      (node (ref "IC3") (pin "27") (pinfunction "TESTJ_27") (pintype "bidirectional"))
    )
    (net (code "65") (name "unconnected-(J2-GNDDTCT-Pad9)") (class "Default")
      (node (ref "J2") (pin "9") (pinfunction "GNDDTCT_9") (pintype "bidirectional"))
    )
    (net (code "66") (name "unconnected-(J2-KEY-Pad7)") (class "Default")
      (node (ref "J2") (pin "7") (pinfunction "KEY_7") (pintype "bidirectional"))
    )
    (net (code "67") (name "unconnected-(J2-NC{slash}TDI-Pad8)") (class "Default")
      (node (ref "J2") (pin "8") (pinfunction "NC/TDI_8") (pintype "bidirectional"))
    )
    (net (code "68") (name "unconnected-(J2-SWO{slash}TDO-Pad6)") (class "Default")
      (node (ref "J2") (pin "6") (pinfunction "SWO/TDO_6") (pintype "bidirectional"))
    )
    (net (code "69") (name "unconnected-(J3-PadGNDBREAK)") (class "Default")
      (node (ref "J3") (pin "GNDBREAK") (pinfunction "GNDBREAK_GNDBREAK") (pintype "bidirectional"))
    )
    (net (code "70") (name "unconnected-(J4-PadGNDBREAK)") (class "Default")
      (node (ref "J4") (pin "GNDBREAK") (pinfunction "GNDBREAK_GNDBREAK") (pintype "bidirectional"))
    )
    (net (code "71") (name "unconnected-(MCP9808-VOUT-Pad3)") (class "Default")
      (node (ref "MCP9808") (pin "3") (pinfunction "VOUT_3") (pintype "bidirectional"))
    )
    (net (code "72") (name "unconnected-(U1-GNDANA-Pad5)") (class "Default")
      (node (ref "U1") (pin "5") (pinfunction "GNDANA_5") (pintype "bidirectional"))
    )
    (net (code "73") (name "unconnected-(U1-PA02(AIN0{slash}DAC)-Pad3)") (class "Default")
      (node (ref "U1") (pin "3") (pinfunction "PA02(AIN0/DAC)_3") (pintype "bidirectional"))
    )
    (net (code "74") (name "unconnected-(U1-PA03(AIN1{slash}REFA)-Pad4)") (class "Default")
      (node (ref "U1") (pin "4") (pinfunction "PA03(AIN1/REFA)_4") (pintype "bidirectional"))
    )
    (net (code "75") (name "unconnected-(U1-PA04(AIN4{slash}REFB{slash}SER0:0{slash}TC0:0)-Pad9)") (class "Default")
      (node (ref "U1") (pin "9") (pinfunction "PA04(AIN4/REFB/SER0:0/TC0:0)_9") (pintype "bidirectional"))
    )
    (net (code "76") (name "unconnected-(U1-PA06(AIN6{slash}SER0:2{slash}TC1:0)-Pad11)") (class "Default")
      (node (ref "U1") (pin "11") (pinfunction "PA06(AIN6/SER0:2/TC1:0)_11") (pintype "bidirectional"))
    )
    (net (code "77") (name "unconnected-(U1-PA07(AIN7{slash}SER0:3{slash}TC1:1)-Pad12)") (class "Default")
      (node (ref "U1") (pin "12") (pinfunction "PA07(AIN7/SER0:3/TC1:1)_12") (pintype "bidirectional"))
    )
    (net (code "78") (name "unconnected-(U1-PA08(I2C{slash}AIN16{slash}SER0:0+)-Pad13)") (class "Default")
      (node (ref "U1") (pin "13") (pinfunction "PA08(I2C/AIN16/SER0:0+)_13") (pintype "bidirectional"))
    )
    (net (code "79") (name "unconnected-(U1-PA09(I2C{slash}AIN17{slash}SER0:1+)-Pad14)") (class "Default")
      (node (ref "U1") (pin "14") (pinfunction "PA09(I2C/AIN17/SER0:1+)_14") (pintype "bidirectional"))
    )
    (net (code "80") (name "unconnected-(U1-PA10(AIN18{slash}SER0:2+)-Pad15)") (class "Default")
      (node (ref "U1") (pin "15") (pinfunction "PA10(AIN18/SER0:2+)_15") (pintype "bidirectional"))
    )
    (net (code "81") (name "unconnected-(U1-PA11(AIN19{slash}SER0:3+)-Pad16)") (class "Default")
      (node (ref "U1") (pin "16") (pinfunction "PA11(AIN19/SER0:3+)_16") (pintype "bidirectional"))
    )
    (net (code "82") (name "unconnected-(U1-PA12(I2C{slash}SER2:0+)-Pad21)") (class "Default")
      (node (ref "U1") (pin "21") (pinfunction "PA12(I2C/SER2:0+)_21") (pintype "bidirectional"))
    )
    (net (code "83") (name "unconnected-(U1-PA13(I2C{slash}SER2:1+)-Pad22)") (class "Default")
      (node (ref "U1") (pin "22") (pinfunction "PA13(I2C/SER2:1+)_22") (pintype "bidirectional"))
    )
    (net (code "84") (name "unconnected-(U1-PA14(XIN{slash}SER2:2+)-Pad23)") (class "Default")
      (node (ref "U1") (pin "23") (pinfunction "PA14(XIN/SER2:2+)_23") (pintype "bidirectional"))
    )
    (net (code "85") (name "unconnected-(U1-PA15(XOUT{slash}SER2:3+)-Pad24)") (class "Default")
      (node (ref "U1") (pin "24") (pinfunction "PA15(XOUT/SER2:3+)_24") (pintype "bidirectional"))
    )
    (net (code "86") (name "unconnected-(U1-PA16(I2C{slash}SER1:0+)-Pad25)") (class "Default")
      (node (ref "U1") (pin "25") (pinfunction "PA16(I2C/SER1:0+)_25") (pintype "bidirectional"))
    )
    (net (code "87") (name "unconnected-(U1-PA20(SER5:2+)-Pad29)") (class "Default")
      (node (ref "U1") (pin "29") (pinfunction "PA20(SER5:2+)_29") (pintype "bidirectional"))
    )
    (net (code "88") (name "unconnected-(U1-PA27-Pad39)") (class "Default")
      (node (ref "U1") (pin "39") (pinfunction "PA27_39") (pintype "bidirectional"))
    )
    (net (code "89") (name "unconnected-(U1-PA28-Pad41)") (class "Default")
      (node (ref "U1") (pin "41") (pinfunction "PA28_41") (pintype "bidirectional"))
    )
    (net (code "90") (name "unconnected-(U1-PB03(AIN11{slash}SER5:1)-Pad48)") (class "Default")
      (node (ref "U1") (pin "48") (pinfunction "PB03(AIN11/SER5:1)_48") (pintype "bidirectional"))
    )
    (net (code "91") (name "unconnected-(U1-PB09(AIN3{slash}SER4:1{slash}TC4:1)-Pad8)") (class "Default")
      (node (ref "U1") (pin "8") (pinfunction "PB09(AIN3/SER4:1/TC4:1)_8") (pintype "bidirectional"))
    )
    (net (code "92") (name "unconnected-(U1-PB10(SER4:2+)-Pad19)") (class "Default")
      (node (ref "U1") (pin "19") (pinfunction "PB10(SER4:2+)_19") (pintype "bidirectional"))
    )
    (net (code "93") (name "unconnected-(U1-PB11(SER4:3+)-Pad20)") (class "Default")
      (node (ref "U1") (pin "20") (pinfunction "PB11(SER4:3+)_20") (pintype "bidirectional"))
    )
    (net (code "94") (name "unconnected-(U1-PB22(SER5:2+)-Pad37)") (class "Default")
      (node (ref "U1") (pin "37") (pinfunction "PB22(SER5:2+)_37") (pintype "bidirectional"))
    )
    (net (code "95") (name "unconnected-(U1-PB23(SER5:3+)-Pad38)") (class "Default")
      (node (ref "U1") (pin "38") (pinfunction "PB23(SER5:3+)_38") (pintype "bidirectional"))
    )
    (net (code "96") (name "unconnected-(X2-Pad4)") (class "Default")
      (node (ref "X2") (pin "4") (pinfunction "4_4") (pintype "passive"))
    )
  )
)
